# Relay_Ctrl.net
KiCad netlist of a schematic drawn in Altium Designer
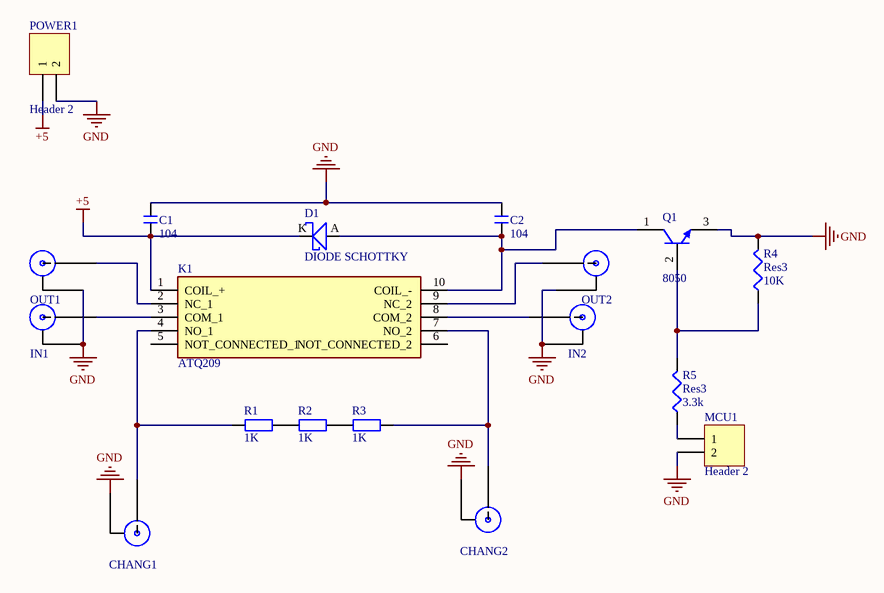
[diagram p0: Relay_Ctrl.SchDoc]

(export (version "E")
  (design (tool "Eeschema 10.0.6"))
  (components
    (comp (ref "C1")
      (value "104")
      (footprint "0805D")
      (description "无极性贴片电容")
      (fields (field (name "版权归属") "源创客"))
      (libsource (lib "Lavida_Library") (part "C"))
    )
    (comp (ref "C2")
      (value "104")
      (footprint "0805D")
      (description "无极性贴片电容")
      (fields (field (name "版权归属") "源创客"))
      (libsource (lib "Lavida_Library") (part "C"))
    )
    (comp (ref "CHANG1") (value "1") (footprint "SMA1") (libsource (lib "Lavida_Library") (part "SMA-side")))
    (comp (ref "CHANG2") (value "1") (footprint "SMA1") (libsource (lib "Lavida_Library") (part "SMA-side")))
    (comp (ref "D1") (value "DIODE SCHOTTKY") (libsource (lib "WXHSCH") (part "DIODE SCHOTTKY")))
    (comp (ref "IN1") (value "1") (footprint "SMA1") (libsource (lib "Lavida_Library") (part "SMA-side")))
    (comp (ref "IN2") (value "1") (footprint "SMA1") (libsource (lib "Lavida_Library") (part "SMA-side")))
    (comp (ref "K1")
      (value "ATQ209")
      (footprint "SamacSys:ATQ209")
      (description "Relay or Contactor")
      (libsource (lib "SamacSys") (part "ATQ209"))
    )
    (comp (ref "MCU1")
      (value "Header 2")
      (footprint "HDR1X2")
      (description "Header, 2-Pin")
      (fields (field (name "PUBLISHER") "Altium Limited"))
      (libsource (lib "") (part "Header 2_1"))
    )
    (comp (ref "OUT1") (value "1") (footprint "SMA1") (libsource (lib "Lavida_Library") (part "SMA-side")))
    (comp (ref "OUT2") (value "1") (footprint "SMA1") (libsource (lib "Lavida_Library") (part "SMA-side")))
    (comp (ref "POWER1")
      (value "Header 2")
      (footprint "HDR1X2")
      (description "Header, 2-Pin")
      (fields (field (name "PUBLISHER") "Altium Limited"))
      (libsource (lib "Miscellaneous Connectors") (part "Header 2"))
    )
    (comp (ref "Q1")
      (value "8050")
      (footprint "SOT-23")
      (description "NPN Bipolar Transistor")
      (fields (field (name "PUBLISHER") "Altium Limited"))
      (libsource (lib "Miscellaneous Devices") (part "NPN"))
    )
    (comp (ref "R1")
      (value "1K")
      (footprint "0805D")
      (description "贴片电阻")
      (fields (field (name "版权归属") "源创客"))
      (libsource (lib "Lavida_Library") (part "R"))
    )
    (comp (ref "R2")
      (value "1K")
      (footprint "0805D")
      (description "贴片电阻")
      (fields (field (name "版权归属") "源创客"))
      (libsource (lib "Lavida_Library") (part "R"))
    )
    (comp (ref "R3")
      (value "1K")
      (footprint "0805D")
      (description "贴片电阻")
      (fields (field (name "版权归属") "源创客"))
      (libsource (lib "Lavida_Library") (part "R"))
    )
    (comp (ref "R4")
      (value "Res3")
      (footprint "0805D")
      (description "Resistor")
      (fields (field (name "ALTIUM_VALUE") "10K") (field (name "PUBLISHER") "Altium Limited"))
      (libsource (lib "Miscellaneous Devices") (part "Res3"))
    )
    (comp (ref "R5")
      (value "Res3")
      (footprint "0805D")
      (description "Resistor")
      (fields (field (name "ALTIUM_VALUE") "3.3k") (field (name "PUBLISHER") "Altium Limited"))
      (libsource (lib "Miscellaneous Devices") (part "Res3"))
    )
  )
  (nets
    (net (code "1") (name "+5") (class "Default")
      (node (ref "C1") (pin "1") (pinfunction "1_1") (pintype "passive"))
      (node (ref "D1") (pin "K") (pinfunction "CATHODE_K") (pintype "passive"))
      (node (ref "K1") (pin "1") (pinfunction "COIL_+_1") (pintype "passive"))
      (node (ref "POWER1") (pin "1") (pinfunction "1_1") (pintype "passive"))
    )
    (net (code "2") (name "GND") (class "Default")
      (node (ref "C1") (pin "2") (pinfunction "2_2") (pintype "passive"))
      (node (ref "C2") (pin "2") (pinfunction "2_2") (pintype "passive"))
      (node (ref "CHANG1") (pin "2") (pinfunction "GND_2") (pintype "passive"))
      (node (ref "CHANG2") (pin "2") (pinfunction "GND_2") (pintype "passive"))
      (node (ref "IN1") (pin "2") (pinfunction "GND_2") (pintype "passive"))
      (node (ref "IN2") (pin "2") (pinfunction "GND_2") (pintype "passive"))
      (node (ref "MCU1") (pin "2") (pinfunction "2_2") (pintype "passive"))
      (node (ref "OUT1") (pin "2") (pinfunction "GND_2") (pintype "passive"))
      (node (ref "OUT2") (pin "2") (pinfunction "GND_2") (pintype "passive"))
      (node (ref "POWER1") (pin "2") (pinfunction "2_2") (pintype "passive"))
      (node (ref "Q1") (pin "3") (pinfunction "E_3") (pintype "passive"))
      (node (ref "R4") (pin "2") (pinfunction "2_2") (pintype "passive"))
    )
    (net (code "3") (name "Net-(CHANG1-sign)") (class "Default")
      (node (ref "CHANG1") (pin "1") (pinfunction "sign_1") (pintype "passive"))
      (node (ref "K1") (pin "4") (pinfunction "NO_1_4") (pintype "passive"))
      (node (ref "R1") (pin "1") (pinfunction "1_1") (pintype "passive"))
    )
    (net (code "4") (name "Net-(CHANG2-sign)") (class "Default")
      (node (ref "CHANG2") (pin "1") (pinfunction "sign_1") (pintype "passive"))
      (node (ref "K1") (pin "7") (pinfunction "NO_2_7") (pintype "passive"))
      (node (ref "R3") (pin "2") (pinfunction "2_2") (pintype "passive"))
    )
    (net (code "5") (name "Net-(D1-ANODE)") (class "Default")
      (node (ref "C2") (pin "1") (pinfunction "1_1") (pintype "passive"))
      (node (ref "D1") (pin "A") (pinfunction "ANODE_A") (pintype "passive"))
      (node (ref "K1") (pin "10") (pinfunction "COIL_-_10") (pintype "passive"))
      (node (ref "Q1") (pin "1") (pinfunction "C_1") (pintype "passive"))
    )
    (net (code "6") (name "Net-(IN1-sign)") (class "Default")
      (node (ref "IN1") (pin "1") (pinfunction "sign_1") (pintype "passive"))
      (node (ref "K1") (pin "3") (pinfunction "COM_1_3") (pintype "passive"))
    )
    (net (code "7") (name "Net-(IN2-sign)") (class "Default")
      (node (ref "IN2") (pin "1") (pinfunction "sign_1") (pintype "passive"))
      (node (ref "K1") (pin "8") (pinfunction "COM_2_8") (pintype "passive"))
    )
    (net (code "8") (name "Net-(K1-NC_1)") (class "Default")
      (node (ref "K1") (pin "2") (pinfunction "NC_1_2") (pintype "passive"))
      (node (ref "OUT1") (pin "1") (pinfunction "sign_1") (pintype "passive"))
    )
    (net (code "9") (name "Net-(K1-NC_2)") (class "Default")
      (node (ref "K1") (pin "9") (pinfunction "NC_2_9") (pintype "passive"))
      (node (ref "OUT2") (pin "1") (pinfunction "sign_1") (pintype "passive"))
    )
    (net (code "10") (name "Net-(MCU1-Pad1)") (class "Default")
      (node (ref "MCU1") (pin "1") (pinfunction "1_1") (pintype "passive"))
      (node (ref "R5") (pin "1") (pinfunction "1_1") (pintype "passive"))
    )
    (net (code "11") (name "Net-(Q1-B)") (class "Default")
      (node (ref "Q1") (pin "2") (pinfunction "B_2") (pintype "passive"))
      (node (ref "R4") (pin "1") (pinfunction "1_1") (pintype "passive"))
      (node (ref "R5") (pin "2") (pinfunction "2_2") (pintype "passive"))
    )
    (net (code "12") (name "Net-(R1-Pad2)") (class "Default")
      (node (ref "R1") (pin "2") (pinfunction "2_2") (pintype "passive"))
      (node (ref "R2") (pin "1") (pinfunction "1_1") (pintype "passive"))
    )
    (net (code "13") (name "Net-(R2-Pad2)") (class "Default")
      (node (ref "R2") (pin "2") (pinfunction "2_2") (pintype "passive"))
      (node (ref "R3") (pin "1") (pinfunction "1_1") (pintype "passive"))
    )
    (net (code "14") (name "unconnected-(K1-NOT_CONNECTED_1-Pad5)") (class "Default")
      (node (ref "K1") (pin "5") (pinfunction "NOT_CONNECTED_1_5") (pintype "passive"))
    )
    (net (code "15") (name "unconnected-(K1-NOT_CONNECTED_2-Pad6)") (class "Default")
      (node (ref "K1") (pin "6") (pinfunction "NOT_CONNECTED_2_6") (pintype "passive"))
    )
  )
)
